# LT8335_6V.net
KiCad netlist of a schematic drawn in EAGLE
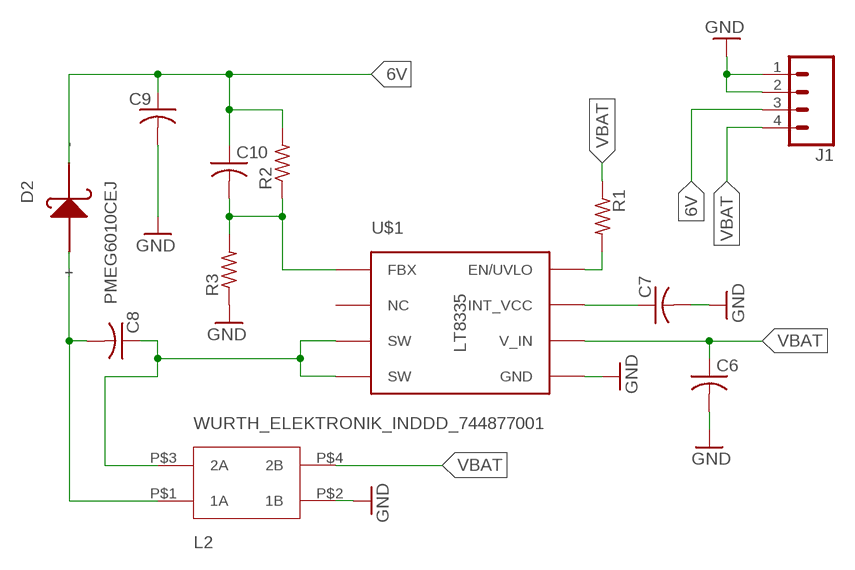
[diagram p0: schematic, sheet 1]

(export (version "E")
  (design (tool "Eeschema 10.0.6"))
  (components
    (comp (ref "C6")
      (value "C-USC0805")
      (footprint "eagle-import:C0805")
      (libsource (lib "eagle-import") (part "C-USC0805"))
    )
    (comp (ref "C7")
      (value "C-USC0805")
      (footprint "eagle-import:C0805")
      (libsource (lib "eagle-import") (part "C-USC0805"))
    )
    (comp (ref "C8")
      (value "C-USC0805")
      (footprint "eagle-import:C0805")
      (libsource (lib "eagle-import") (part "C-USC0805"))
    )
    (comp (ref "C9")
      (value "C-USC0805")
      (footprint "eagle-import:C0805")
      (libsource (lib "eagle-import") (part "C-USC0805"))
    )
    (comp (ref "C10")
      (value "C-USC0805")
      (footprint "eagle-import:C0805")
      (libsource (lib "eagle-import") (part "C-USC0805"))
    )
    (comp (ref "D2")
      (value "PMEG6010CEJ")
      (footprint "eagle-import:SC-90")
      (libsource (lib "eagle-import") (part "PMEG6010CEJ"))
    )
    (comp (ref "J1")
      (value "CONN_04LOCK")
      (footprint "eagle-import:1X04_LOCK")
      (libsource (lib "eagle-import") (part "CONN_04LOCK"))
    )
    (comp (ref "L2")
      (value "WURTH_ELEKTRONIK_INDDD_744877001")
      (footprint "eagle-import:WURTH_ELEKTRONIK_INDDD_744877001")
      (libsource (lib "eagle-import") (part "WURTH_ELEKTRONIK_INDDD_744877001"))
    )
    (comp (ref "R1")
      (value "R-US_R0805")
      (footprint "eagle-import:R0805")
      (libsource (lib "eagle-import") (part "R-US_R0805"))
    )
    (comp (ref "R2")
      (value "R-US_R0805")
      (footprint "eagle-import:R0805")
      (libsource (lib "eagle-import") (part "R-US_R0805"))
    )
    (comp (ref "R3")
      (value "R-US_R0805")
      (footprint "eagle-import:R0805")
      (libsource (lib "eagle-import") (part "R-US_R0805"))
    )
    (comp (ref "U$1")
      (value "LT8335")
      (footprint "eagle-import:DDB")
      (libsource (lib "eagle-import") (part "LT8335"))
    )
  )
  (nets
    (net (code "1") (name "6V") (class "Default")
      (node (ref "C10") (pin "1") (pinfunction "1_1") (pintype "passive"))
      (node (ref "C9") (pin "1") (pinfunction "1_1") (pintype "passive"))
      (node (ref "D2") (pin "P$2") (pinfunction "-_P$2") (pintype "bidirectional"))
      (node (ref "J1") (pin "3") (pinfunction "3_3") (pintype "passive"))
      (node (ref "R2") (pin "2") (pinfunction "2_2") (pintype "passive"))
    )
    (net (code "2") (name "GND") (class "Default")
      (node (ref "C6") (pin "2") (pinfunction "2_2") (pintype "passive"))
      (node (ref "C7") (pin "2") (pinfunction "2_2") (pintype "passive"))
      (node (ref "C9") (pin "2") (pinfunction "2_2") (pintype "passive"))
      (node (ref "J1") (pin "1") (pinfunction "1_1") (pintype "passive"))
      (node (ref "J1") (pin "2") (pinfunction "2_2") (pintype "passive"))
      (node (ref "L2") (pin "P$2") (pinfunction "1B_P$2") (pintype "bidirectional"))
      (node (ref "R3") (pin "1") (pinfunction "1_1") (pintype "passive"))
      (node (ref "U$1") (pin "GND") (pinfunction "GND_GND") (pintype "bidirectional"))
      (node (ref "U$1") (pin "P$5") (pinfunction "GND_P$5") (pintype "bidirectional"))
    )
    (net (code "3") (name "Net-(D2-+)") (class "Default")
      (node (ref "C8") (pin "2") (pinfunction "2_2") (pintype "passive"))
      (node (ref "D2") (pin "P$1") (pinfunction "+_P$1") (pintype "bidirectional"))
      (node (ref "L2") (pin "P$1") (pinfunction "1A_P$1") (pintype "bidirectional"))
    )
    (net (code "4") (name "Net-(L2-2A)") (class "Default")
      (node (ref "C8") (pin "1") (pinfunction "1_1") (pintype "passive"))
      (node (ref "L2") (pin "P$3") (pinfunction "2A_P$3") (pintype "bidirectional"))
      (node (ref "U$1") (pin "P$3") (pinfunction "SW_P$3") (pintype "bidirectional"))
      (node (ref "U$1") (pin "P$4") (pinfunction "SW_P$4") (pintype "bidirectional"))
    )
    (net (code "5") (name "Net-(U$1-EN{slash}UVLO)") (class "Default")
      (node (ref "R1") (pin "2") (pinfunction "2_2") (pintype "passive"))
      (node (ref "U$1") (pin "P$8") (pinfunction "EN/UVLO_P$8") (pintype "bidirectional"))
    )
    (net (code "6") (name "Net-(U$1-FBX)") (class "Default")
      (node (ref "C10") (pin "2") (pinfunction "2_2") (pintype "passive"))
      (node (ref "R2") (pin "1") (pinfunction "1_1") (pintype "passive"))
      (node (ref "R3") (pin "2") (pinfunction "2_2") (pintype "passive"))
      (node (ref "U$1") (pin "P$1") (pinfunction "FBX_P$1") (pintype "bidirectional"))
    )
    (net (code "7") (name "Net-(U$1-INT_VCC)") (class "Default")
      (node (ref "C7") (pin "1") (pinfunction "1_1") (pintype "passive"))
      (node (ref "U$1") (pin "P$7") (pinfunction "INT_VCC_P$7") (pintype "bidirectional"))
    )
    (net (code "8") (name "VBAT") (class "Default")
      (node (ref "C6") (pin "1") (pinfunction "1_1") (pintype "passive"))
      (node (ref "J1") (pin "4") (pinfunction "4_4") (pintype "passive"))
      (node (ref "L2") (pin "P$4") (pinfunction "2B_P$4") (pintype "bidirectional"))
      (node (ref "R1") (pin "1") (pinfunction "1_1") (pintype "passive"))
      (node (ref "U$1") (pin "P$6") (pinfunction "V_IN_P$6") (pintype "bidirectional"))
    )
    (net (code "9") (name "unconnected-(U$1-NC-PadP$2)") (class "Default")
      (node (ref "U$1") (pin "P$2") (pinfunction "NC_P$2") (pintype "bidirectional"))
    )
  )
)
